# LEDs.net
KiCad netlist of a schematic drawn in Altium Designer
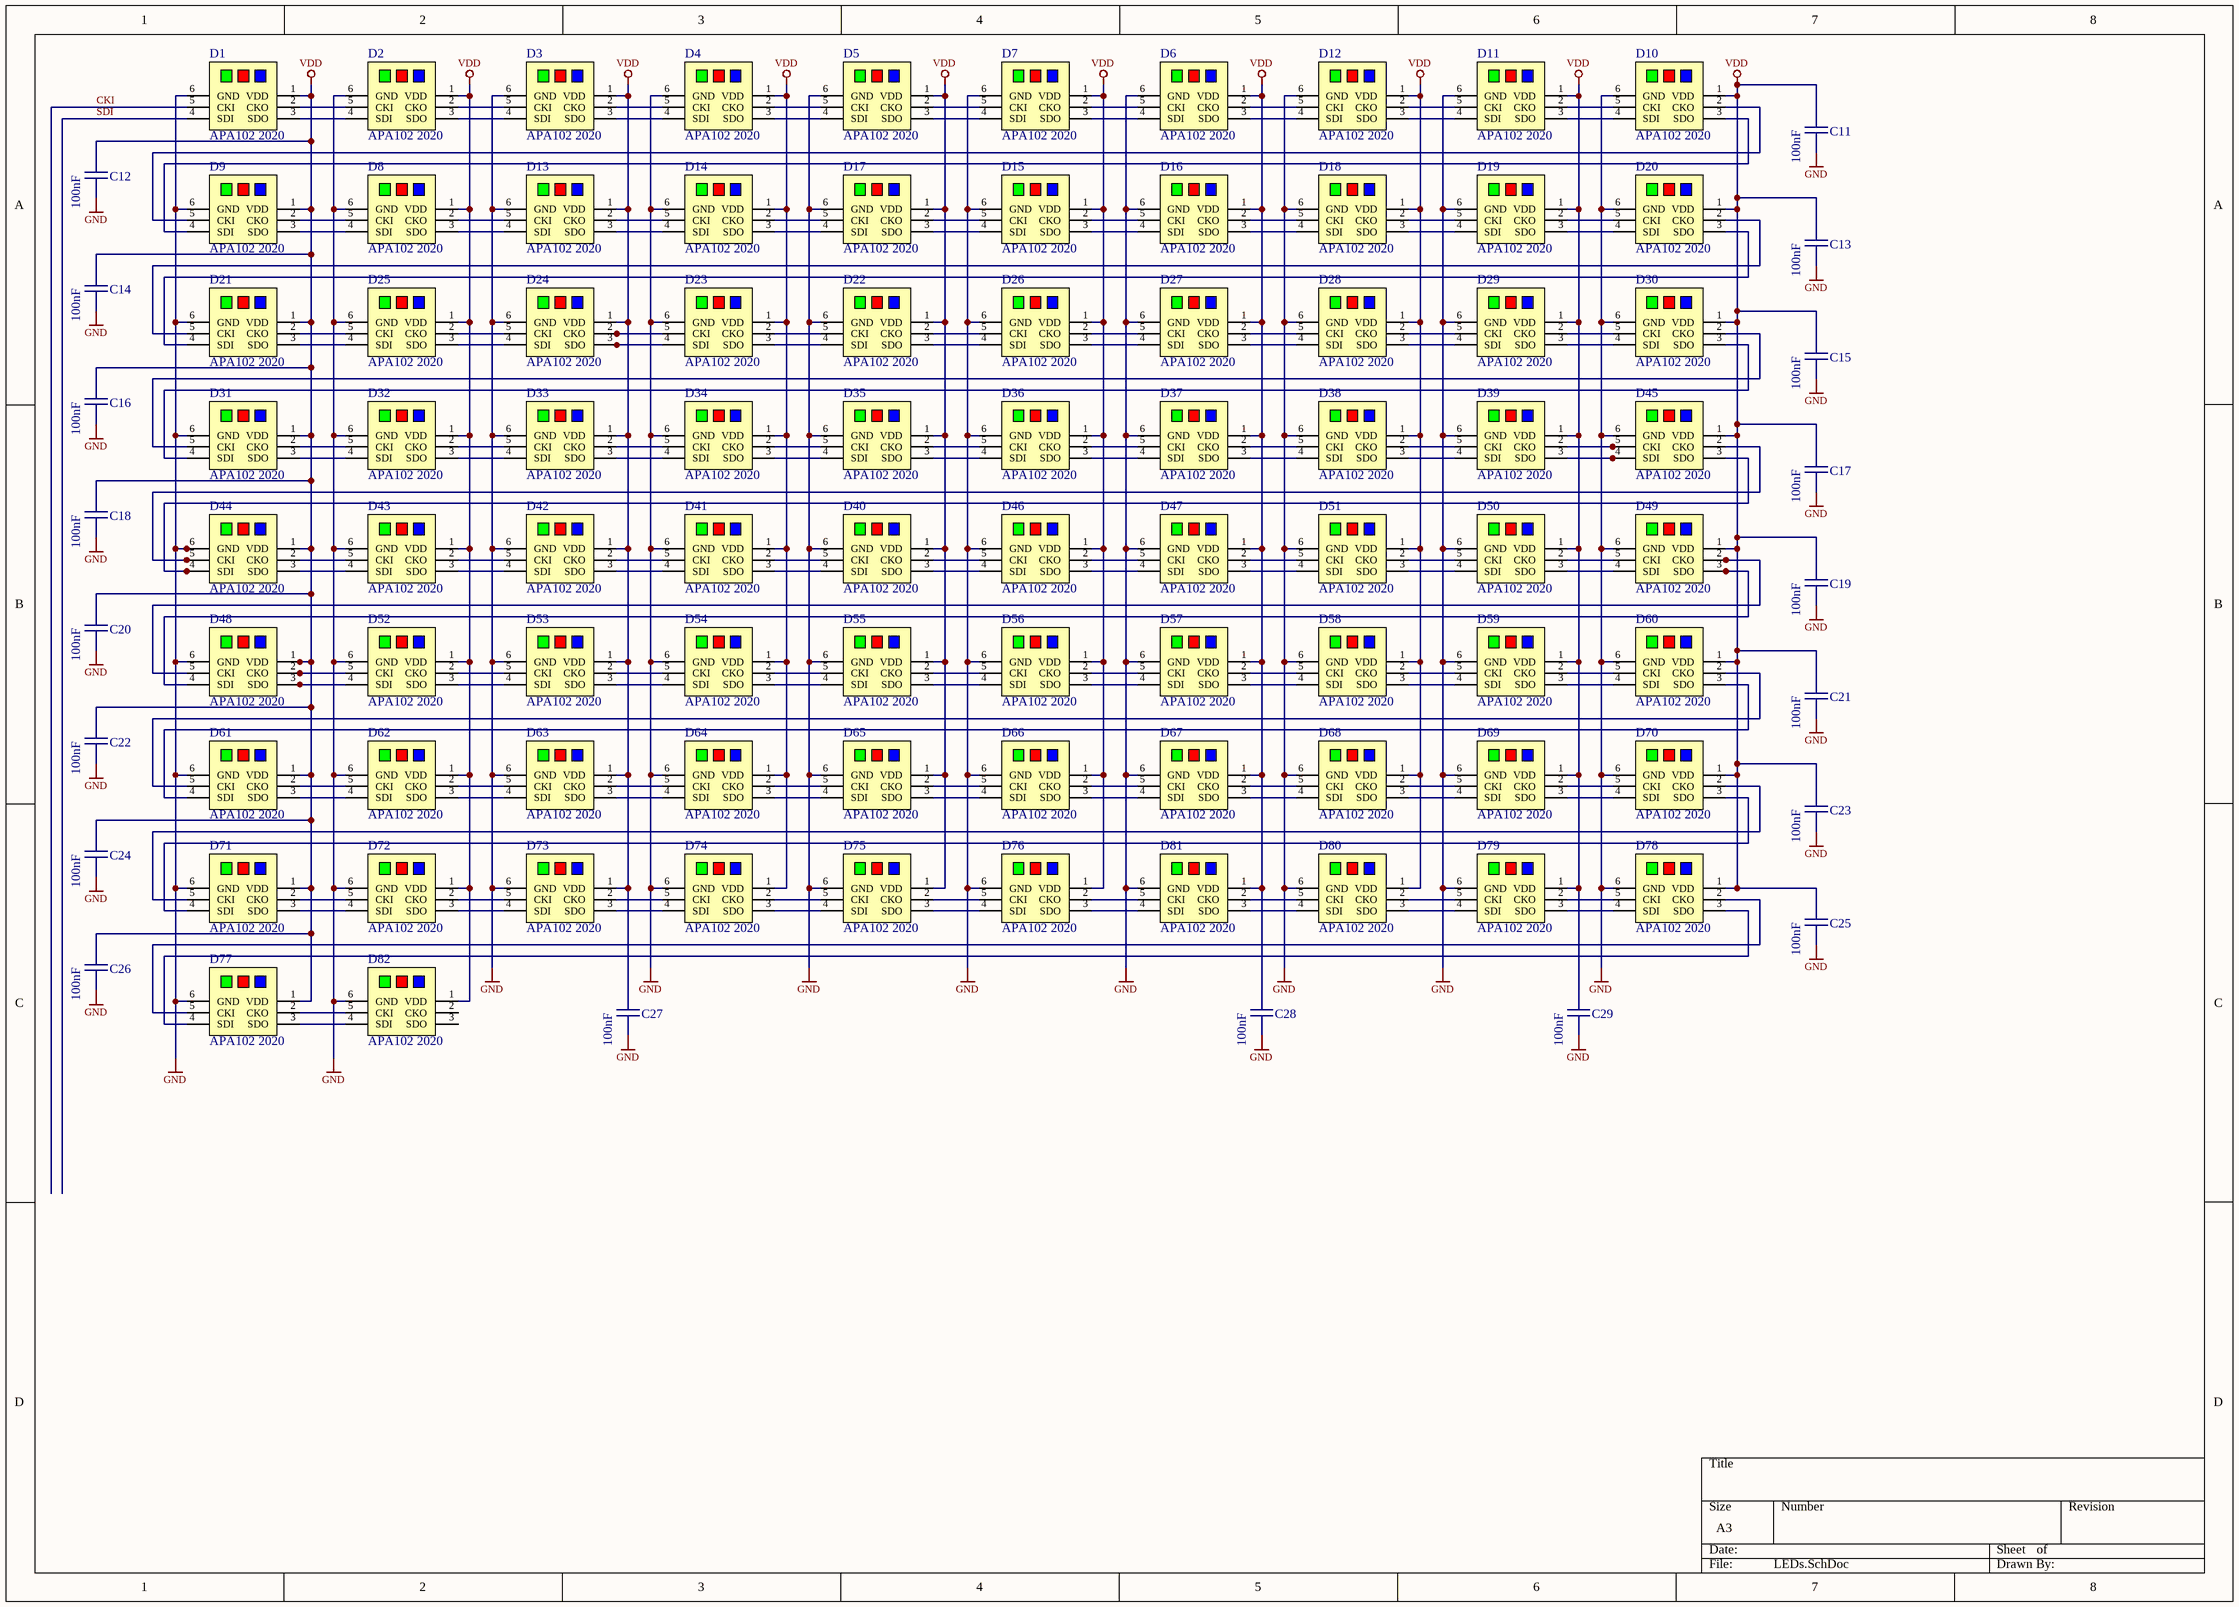
[diagram p0: LEDs.SchDoc]

(export (version "E")
  (design (tool "Eeschema 10.0.6"))
  (components
    (comp (ref "C11")
      (value "100nF")
      (footprint "CAPC0603(1608)55_N")
      (libsource (lib "OVLib_64") (part "CAP"))
    )
    (comp (ref "C12")
      (value "100nF")
      (footprint "CAPC0603(1608)55_N")
      (libsource (lib "OVLib_64") (part "CAP"))
    )
    (comp (ref "C13")
      (value "100nF")
      (footprint "CAPC0603(1608)55_N")
      (libsource (lib "OVLib_64") (part "CAP"))
    )
    (comp (ref "C14")
      (value "100nF")
      (footprint "CAPC0603(1608)55_N")
      (libsource (lib "OVLib_64") (part "CAP"))
    )
    (comp (ref "C15")
      (value "100nF")
      (footprint "CAPC0603(1608)55_N")
      (libsource (lib "OVLib_64") (part "CAP"))
    )
    (comp (ref "C16")
      (value "100nF")
      (footprint "CAPC0603(1608)55_N")
      (libsource (lib "OVLib_64") (part "CAP"))
    )
    (comp (ref "C17")
      (value "100nF")
      (footprint "CAPC0603(1608)55_N")
      (libsource (lib "OVLib_64") (part "CAP"))
    )
    (comp (ref "C18")
      (value "100nF")
      (footprint "CAPC0603(1608)55_N")
      (libsource (lib "OVLib_64") (part "CAP"))
    )
    (comp (ref "C19")
      (value "100nF")
      (footprint "CAPC0603(1608)55_N")
      (libsource (lib "OVLib_64") (part "CAP"))
    )
    (comp (ref "C20")
      (value "100nF")
      (footprint "CAPC0603(1608)55_N")
      (libsource (lib "OVLib_64") (part "CAP"))
    )
    (comp (ref "C21")
      (value "100nF")
      (footprint "CAPC0603(1608)55_N")
      (libsource (lib "OVLib_64") (part "CAP"))
    )
    (comp (ref "C22")
      (value "100nF")
      (footprint "CAPC0603(1608)55_N")
      (libsource (lib "OVLib_64") (part "CAP"))
    )
    (comp (ref "C23")
      (value "100nF")
      (footprint "CAPC0603(1608)55_N")
      (libsource (lib "OVLib_64") (part "CAP"))
    )
    (comp (ref "C24")
      (value "100nF")
      (footprint "CAPC0603(1608)55_N")
      (libsource (lib "OVLib_64") (part "CAP"))
    )
    (comp (ref "C25")
      (value "100nF")
      (footprint "CAPC0603(1608)55_N")
      (libsource (lib "OVLib_64") (part "CAP"))
    )
    (comp (ref "C26")
      (value "100nF")
      (footprint "CAPC0603(1608)55_N")
      (libsource (lib "OVLib_64") (part "CAP"))
    )
    (comp (ref "C27")
      (value "100nF")
      (footprint "CAPC0603(1608)55_N")
      (libsource (lib "OVLib_64") (part "CAP"))
    )
    (comp (ref "C28")
      (value "100nF")
      (footprint "CAPC0603(1608)55_N")
      (libsource (lib "OVLib_64") (part "CAP"))
    )
    (comp (ref "C29")
      (value "100nF")
      (footprint "CAPC0603(1608)55_N")
      (libsource (lib "OVLib_64") (part "CAP"))
    )
    (comp (ref "D1")
      (value "APA102 2020")
      (footprint "APA_RGB_LED_2020")
      (libsource (lib "OVLib_64") (part "LED_RGB_APA102"))
    )
    (comp (ref "D2")
      (value "APA102 2020")
      (footprint "APA_RGB_LED_2020")
      (libsource (lib "OVLib_64") (part "LED_RGB_APA102"))
    )
    (comp (ref "D3")
      (value "APA102 2020")
      (footprint "APA_RGB_LED_2020")
      (libsource (lib "OVLib_64") (part "LED_RGB_APA102"))
    )
    (comp (ref "D4")
      (value "APA102 2020")
      (footprint "APA_RGB_LED_2020")
      (libsource (lib "OVLib_64") (part "LED_RGB_APA102"))
    )
    (comp (ref "D5")
      (value "APA102 2020")
      (footprint "APA_RGB_LED_2020")
      (libsource (lib "OVLib_64") (part "LED_RGB_APA102"))
    )
    (comp (ref "D6")
      (value "APA102 2020")
      (footprint "APA_RGB_LED_2020")
      (libsource (lib "OVLib_64") (part "LED_RGB_APA102"))
    )
    (comp (ref "D7")
      (value "APA102 2020")
      (footprint "APA_RGB_LED_2020")
      (libsource (lib "OVLib_64") (part "LED_RGB_APA102"))
    )
    (comp (ref "D8")
      (value "APA102 2020")
      (footprint "APA_RGB_LED_2020")
      (libsource (lib "OVLib_64") (part "LED_RGB_APA102"))
    )
    (comp (ref "D9")
      (value "APA102 2020")
      (footprint "APA_RGB_LED_2020")
      (libsource (lib "OVLib_64") (part "LED_RGB_APA102"))
    )
    (comp (ref "D10")
      (value "APA102 2020")
      (footprint "APA_RGB_LED_2020")
      (libsource (lib "OVLib_64") (part "LED_RGB_APA102"))
    )
    (comp (ref "D11")
      (value "APA102 2020")
      (footprint "APA_RGB_LED_2020")
      (libsource (lib "OVLib_64") (part "LED_RGB_APA102"))
    )
    (comp (ref "D12")
      (value "APA102 2020")
      (footprint "APA_RGB_LED_2020")
      (libsource (lib "OVLib_64") (part "LED_RGB_APA102"))
    )
    (comp (ref "D13")
      (value "APA102 2020")
      (footprint "APA_RGB_LED_2020")
      (libsource (lib "OVLib_64") (part "LED_RGB_APA102"))
    )
    (comp (ref "D14")
      (value "APA102 2020")
      (footprint "APA_RGB_LED_2020")
      (libsource (lib "OVLib_64") (part "LED_RGB_APA102"))
    )
    (comp (ref "D15")
      (value "APA102 2020")
      (footprint "APA_RGB_LED_2020")
      (libsource (lib "OVLib_64") (part "LED_RGB_APA102"))
    )
    (comp (ref "D16")
      (value "APA102 2020")
      (footprint "APA_RGB_LED_2020")
      (libsource (lib "OVLib_64") (part "LED_RGB_APA102"))
    )
    (comp (ref "D17")
      (value "APA102 2020")
      (footprint "APA_RGB_LED_2020")
      (libsource (lib "OVLib_64") (part "LED_RGB_APA102"))
    )
    (comp (ref "D18")
      (value "APA102 2020")
      (footprint "APA_RGB_LED_2020")
      (libsource (lib "OVLib_64") (part "LED_RGB_APA102"))
    )
    (comp (ref "D19")
      (value "APA102 2020")
      (footprint "APA_RGB_LED_2020")
      (libsource (lib "OVLib_64") (part "LED_RGB_APA102"))
    )
    (comp (ref "D20")
      (value "APA102 2020")
      (footprint "APA_RGB_LED_2020")
      (libsource (lib "OVLib_64") (part "LED_RGB_APA102"))
    )
    (comp (ref "D21")
      (value "APA102 2020")
      (footprint "APA_RGB_LED_2020")
      (libsource (lib "OVLib_64") (part "LED_RGB_APA102"))
    )
    (comp (ref "D22")
      (value "APA102 2020")
      (footprint "APA_RGB_LED_2020")
      (libsource (lib "OVLib_64") (part "LED_RGB_APA102"))
    )
    (comp (ref "D23")
      (value "APA102 2020")
      (footprint "APA_RGB_LED_2020")
      (libsource (lib "OVLib_64") (part "LED_RGB_APA102"))
    )
    (comp (ref "D24")
      (value "APA102 2020")
      (footprint "APA_RGB_LED_2020")
      (libsource (lib "OVLib_64") (part "LED_RGB_APA102"))
    )
    (comp (ref "D25")
      (value "APA102 2020")
      (footprint "APA_RGB_LED_2020")
      (libsource (lib "OVLib_64") (part "LED_RGB_APA102"))
    )
    (comp (ref "D26")
      (value "APA102 2020")
      (footprint "APA_RGB_LED_2020")
      (libsource (lib "OVLib_64") (part "LED_RGB_APA102"))
    )
    (comp (ref "D27")
      (value "APA102 2020")
      (footprint "APA_RGB_LED_2020")
      (libsource (lib "OVLib_64") (part "LED_RGB_APA102"))
    )
    (comp (ref "D28")
      (value "APA102 2020")
      (footprint "APA_RGB_LED_2020")
      (libsource (lib "OVLib_64") (part "LED_RGB_APA102"))
    )
    (comp (ref "D29")
      (value "APA102 2020")
      (footprint "APA_RGB_LED_2020")
      (libsource (lib "OVLib_64") (part "LED_RGB_APA102"))
    )
    (comp (ref "D30")
      (value "APA102 2020")
      (footprint "APA_RGB_LED_2020")
      (libsource (lib "OVLib_64") (part "LED_RGB_APA102"))
    )
    (comp (ref "D31")
      (value "APA102 2020")
      (footprint "APA_RGB_LED_2020")
      (libsource (lib "OVLib_64") (part "LED_RGB_APA102"))
    )
    (comp (ref "D32")
      (value "APA102 2020")
      (footprint "APA_RGB_LED_2020")
      (libsource (lib "OVLib_64") (part "LED_RGB_APA102"))
    )
    (comp (ref "D33")
      (value "APA102 2020")
      (footprint "APA_RGB_LED_2020")
      (libsource (lib "OVLib_64") (part "LED_RGB_APA102"))
    )
    (comp (ref "D34")
      (value "APA102 2020")
      (footprint "APA_RGB_LED_2020")
      (libsource (lib "OVLib_64") (part "LED_RGB_APA102"))
    )
    (comp (ref "D35")
      (value "APA102 2020")
      (footprint "APA_RGB_LED_2020")
      (libsource (lib "OVLib_64") (part "LED_RGB_APA102"))
    )
    (comp (ref "D36")
      (value "APA102 2020")
      (footprint "APA_RGB_LED_2020")
      (libsource (lib "OVLib_64") (part "LED_RGB_APA102"))
    )
    (comp (ref "D37")
      (value "APA102 2020")
      (footprint "APA_RGB_LED_2020")
      (libsource (lib "OVLib_64") (part "LED_RGB_APA102"))
    )
    (comp (ref "D38")
      (value "APA102 2020")
      (footprint "APA_RGB_LED_2020")
      (libsource (lib "OVLib_64") (part "LED_RGB_APA102"))
    )
    (comp (ref "D39")
      (value "APA102 2020")
      (footprint "APA_RGB_LED_2020")
      (libsource (lib "OVLib_64") (part "LED_RGB_APA102"))
    )
    (comp (ref "D40")
      (value "APA102 2020")
      (footprint "APA_RGB_LED_2020")
      (libsource (lib "OVLib_64") (part "LED_RGB_APA102"))
    )
    (comp (ref "D41")
      (value "APA102 2020")
      (footprint "APA_RGB_LED_2020")
      (libsource (lib "OVLib_64") (part "LED_RGB_APA102"))
    )
    (comp (ref "D42")
      (value "APA102 2020")
      (footprint "APA_RGB_LED_2020")
      (libsource (lib "OVLib_64") (part "LED_RGB_APA102"))
    )
    (comp (ref "D43")
      (value "APA102 2020")
      (footprint "APA_RGB_LED_2020")
      (libsource (lib "OVLib_64") (part "LED_RGB_APA102"))
    )
    (comp (ref "D44")
      (value "APA102 2020")
      (footprint "APA_RGB_LED_2020")
      (libsource (lib "OVLib_64") (part "LED_RGB_APA102"))
    )
    (comp (ref "D45")
      (value "APA102 2020")
      (footprint "APA_RGB_LED_2020")
      (libsource (lib "OVLib_64") (part "LED_RGB_APA102"))
    )
    (comp (ref "D46")
      (value "APA102 2020")
      (footprint "APA_RGB_LED_2020")
      (libsource (lib "OVLib_64") (part "LED_RGB_APA102"))
    )
    (comp (ref "D47")
      (value "APA102 2020")
      (footprint "APA_RGB_LED_2020")
      (libsource (lib "OVLib_64") (part "LED_RGB_APA102"))
    )
    (comp (ref "D48")
      (value "APA102 2020")
      (footprint "APA_RGB_LED_2020")
      (libsource (lib "OVLib_64") (part "LED_RGB_APA102"))
    )
    (comp (ref "D49")
      (value "APA102 2020")
      (footprint "APA_RGB_LED_2020")
      (libsource (lib "OVLib_64") (part "LED_RGB_APA102"))
    )
    (comp (ref "D50")
      (value "APA102 2020")
      (footprint "APA_RGB_LED_2020")
      (libsource (lib "OVLib_64") (part "LED_RGB_APA102"))
    )
    (comp (ref "D51")
      (value "APA102 2020")
      (footprint "APA_RGB_LED_2020")
      (libsource (lib "OVLib_64") (part "LED_RGB_APA102"))
    )
    (comp (ref "D52")
      (value "APA102 2020")
      (footprint "APA_RGB_LED_2020")
      (libsource (lib "OVLib_64") (part "LED_RGB_APA102"))
    )
    (comp (ref "D53")
      (value "APA102 2020")
      (footprint "APA_RGB_LED_2020")
      (libsource (lib "OVLib_64") (part "LED_RGB_APA102"))
    )
    (comp (ref "D54")
      (value "APA102 2020")
      (footprint "APA_RGB_LED_2020")
      (libsource (lib "OVLib_64") (part "LED_RGB_APA102"))
    )
    (comp (ref "D55")
      (value "APA102 2020")
      (footprint "APA_RGB_LED_2020")
      (libsource (lib "OVLib_64") (part "LED_RGB_APA102"))
    )
    (comp (ref "D56")
      (value "APA102 2020")
      (footprint "APA_RGB_LED_2020")
      (libsource (lib "OVLib_64") (part "LED_RGB_APA102"))
    )
    (comp (ref "D57")
      (value "APA102 2020")
      (footprint "APA_RGB_LED_2020")
      (libsource (lib "OVLib_64") (part "LED_RGB_APA102"))
    )
    (comp (ref "D58")
      (value "APA102 2020")
      (footprint "APA_RGB_LED_2020")
      (libsource (lib "OVLib_64") (part "LED_RGB_APA102"))
    )
    (comp (ref "D59")
      (value "APA102 2020")
      (footprint "APA_RGB_LED_2020")
      (libsource (lib "OVLib_64") (part "LED_RGB_APA102"))
    )
    (comp (ref "D60")
      (value "APA102 2020")
      (footprint "APA_RGB_LED_2020")
      (libsource (lib "OVLib_64") (part "LED_RGB_APA102"))
    )
    (comp (ref "D61")
      (value "APA102 2020")
      (footprint "APA_RGB_LED_2020")
      (libsource (lib "OVLib_64") (part "LED_RGB_APA102"))
    )
    (comp (ref "D62")
      (value "APA102 2020")
      (footprint "APA_RGB_LED_2020")
      (libsource (lib "OVLib_64") (part "LED_RGB_APA102"))
    )
    (comp (ref "D63")
      (value "APA102 2020")
      (footprint "APA_RGB_LED_2020")
      (libsource (lib "OVLib_64") (part "LED_RGB_APA102"))
    )
    (comp (ref "D64")
      (value "APA102 2020")
      (footprint "APA_RGB_LED_2020")
      (libsource (lib "OVLib_64") (part "LED_RGB_APA102"))
    )
    (comp (ref "D65")
      (value "APA102 2020")
      (footprint "APA_RGB_LED_2020")
      (libsource (lib "OVLib_64") (part "LED_RGB_APA102"))
    )
    (comp (ref "D66")
      (value "APA102 2020")
      (footprint "APA_RGB_LED_2020")
      (libsource (lib "OVLib_64") (part "LED_RGB_APA102"))
    )
    (comp (ref "D67")
      (value "APA102 2020")
      (footprint "APA_RGB_LED_2020")
      (libsource (lib "OVLib_64") (part "LED_RGB_APA102"))
    )
    (comp (ref "D68")
      (value "APA102 2020")
      (footprint "APA_RGB_LED_2020")
      (libsource (lib "OVLib_64") (part "LED_RGB_APA102"))
    )
    (comp (ref "D69")
      (value "APA102 2020")
      (footprint "APA_RGB_LED_2020")
      (libsource (lib "OVLib_64") (part "LED_RGB_APA102"))
    )
    (comp (ref "D70")
      (value "APA102 2020")
      (footprint "APA_RGB_LED_2020")
      (libsource (lib "OVLib_64") (part "LED_RGB_APA102"))
    )
    (comp (ref "D71")
      (value "APA102 2020")
      (footprint "APA_RGB_LED_2020")
      (libsource (lib "OVLib_64") (part "LED_RGB_APA102"))
    )
    (comp (ref "D72")
      (value "APA102 2020")
      (footprint "APA_RGB_LED_2020")
      (libsource (lib "OVLib_64") (part "LED_RGB_APA102"))
    )
    (comp (ref "D73")
      (value "APA102 2020")
      (footprint "APA_RGB_LED_2020")
      (libsource (lib "OVLib_64") (part "LED_RGB_APA102"))
    )
    (comp (ref "D74")
      (value "APA102 2020")
      (footprint "APA_RGB_LED_2020")
      (libsource (lib "OVLib_64") (part "LED_RGB_APA102"))
    )
    (comp (ref "D75")
      (value "APA102 2020")
      (footprint "APA_RGB_LED_2020")
      (libsource (lib "OVLib_64") (part "LED_RGB_APA102"))
    )
    (comp (ref "D76")
      (value "APA102 2020")
      (footprint "APA_RGB_LED_2020")
      (libsource (lib "OVLib_64") (part "LED_RGB_APA102"))
    )
    (comp (ref "D77")
      (value "APA102 2020")
      (footprint "APA_RGB_LED_2020")
      (libsource (lib "OVLib_64") (part "LED_RGB_APA102"))
    )
    (comp (ref "D78")
      (value "APA102 2020")
      (footprint "APA_RGB_LED_2020")
      (libsource (lib "OVLib_64") (part "LED_RGB_APA102"))
    )
    (comp (ref "D79")
      (value "APA102 2020")
      (footprint "APA_RGB_LED_2020")
      (libsource (lib "OVLib_64") (part "LED_RGB_APA102"))
    )
    (comp (ref "D80")
      (value "APA102 2020")
      (footprint "APA_RGB_LED_2020")
      (libsource (lib "OVLib_64") (part "LED_RGB_APA102"))
    )
    (comp (ref "D81")
      (value "APA102 2020")
      (footprint "APA_RGB_LED_2020")
      (libsource (lib "OVLib_64") (part "LED_RGB_APA102"))
    )
    (comp (ref "D82")
      (value "APA102 2020")
      (footprint "APA_RGB_LED_2020")
      (libsource (lib "OVLib_64") (part "LED_RGB_APA102"))
    )
  )
  (nets
    (net (code "1") (name "/CKI") (class "Default")
      (node (ref "D1") (pin "5") (pinfunction "CKI_5") (pintype "passive"))
    )
    (net (code "2") (name "/SDI") (class "Default")
      (node (ref "D1") (pin "4") (pinfunction "SDI_4") (pintype "passive"))
    )
    (net (code "3") (name "GND") (class "Default")
      (node (ref "C11") (pin "1") (pinfunction "1_1") (pintype "passive"))
      (node (ref "C12") (pin "1") (pinfunction "1_1") (pintype "passive"))
      (node (ref "C13") (pin "1") (pinfunction "1_1") (pintype "passive"))
      (node (ref "C14") (pin "1") (pinfunction "1_1") (pintype "passive"))
      (node (ref "C15") (pin "1") (pinfunction "1_1") (pintype "passive"))
      (node (ref "C16") (pin "1") (pinfunction "1_1") (pintype "passive"))
      (node (ref "C17") (pin "1") (pinfunction "1_1") (pintype "passive"))
      (node (ref "C18") (pin "1") (pinfunction "1_1") (pintype "passive"))
      (node (ref "C19") (pin "1") (pinfunction "1_1") (pintype "passive"))
      (node (ref "C20") (pin "1") (pinfunction "1_1") (pintype "passive"))
      (node (ref "C21") (pin "1") (pinfunction "1_1") (pintype "passive"))
      (node (ref "C22") (pin "1") (pinfunction "1_1") (pintype "passive"))
      (node (ref "C23") (pin "1") (pinfunction "1_1") (pintype "passive"))
      (node (ref "C24") (pin "1") (pinfunction "1_1") (pintype "passive"))
      (node (ref "C25") (pin "1") (pinfunction "1_1") (pintype "passive"))
      (node (ref "C26") (pin "1") (pinfunction "1_1") (pintype "passive"))
      (node (ref "C27") (pin "1") (pinfunction "1_1") (pintype "passive"))
      (node (ref "C28") (pin "1") (pinfunction "1_1") (pintype "passive"))
      (node (ref "C29") (pin "1") (pinfunction "1_1") (pintype "passive"))
      (node (ref "D1") (pin "6") (pinfunction "GND_6") (pintype "passive"))
      (node (ref "D10") (pin "6") (pinfunction "GND_6") (pintype "passive"))
      (node (ref "D11") (pin "6") (pinfunction "GND_6") (pintype "passive"))
      (node (ref "D12") (pin "6") (pinfunction "GND_6") (pintype "passive"))
      (node (ref "D13") (pin "6") (pinfunction "GND_6") (pintype "passive"))
      (node (ref "D14") (pin "6") (pinfunction "GND_6") (pintype "passive"))
      (node (ref "D15") (pin "6") (pinfunction "GND_6") (pintype "passive"))
      (node (ref "D16") (pin "6") (pinfunction "GND_6") (pintype "passive"))
      (node (ref "D17") (pin "6") (pinfunction "GND_6") (pintype "passive"))
      (node (ref "D18") (pin "6") (pinfunction "GND_6") (pintype "passive"))
      (node (ref "D19") (pin "6") (pinfunction "GND_6") (pintype "passive"))
      (node (ref "D2") (pin "6") (pinfunction "GND_6") (pintype "passive"))
      (node (ref "D20") (pin "6") (pinfunction "GND_6") (pintype "passive"))
      (node (ref "D21") (pin "6") (pinfunction "GND_6") (pintype "passive"))
      (node (ref "D22") (pin "6") (pinfunction "GND_6") (pintype "passive"))
      (node (ref "D23") (pin "6") (pinfunction "GND_6") (pintype "passive"))
      (node (ref "D24") (pin "6") (pinfunction "GND_6") (pintype "passive"))
      (node (ref "D25") (pin "6") (pinfunction "GND_6") (pintype "passive"))
      (node (ref "D26") (pin "6") (pinfunction "GND_6") (pintype "passive"))
      (node (ref "D27") (pin "6") (pinfunction "GND_6") (pintype "passive"))
      (node (ref "D28") (pin "6") (pinfunction "GND_6") (pintype "passive"))
      (node (ref "D29") (pin "6") (pinfunction "GND_6") (pintype "passive"))
      (node (ref "D3") (pin "6") (pinfunction "GND_6") (pintype "passive"))
      (node (ref "D30") (pin "6") (pinfunction "GND_6") (pintype "passive"))
      (node (ref "D31") (pin "6") (pinfunction "GND_6") (pintype "passive"))
      (node (ref "D32") (pin "6") (pinfunction "GND_6") (pintype "passive"))
      (node (ref "D33") (pin "6") (pinfunction "GND_6") (pintype "passive"))
      (node (ref "D34") (pin "6") (pinfunction "GND_6") (pintype "passive"))
      (node (ref "D35") (pin "6") (pinfunction "GND_6") (pintype "passive"))
      (node (ref "D36") (pin "6") (pinfunction "GND_6") (pintype "passive"))
      (node (ref "D37") (pin "6") (pinfunction "GND_6") (pintype "passive"))
      (node (ref "D38") (pin "6") (pinfunction "GND_6") (pintype "passive"))
      (node (ref "D39") (pin "6") (pinfunction "GND_6") (pintype "passive"))
      (node (ref "D4") (pin "6") (pinfunction "GND_6") (pintype "passive"))
      (node (ref "D40") (pin "6") (pinfunction "GND_6") (pintype "passive"))
      (node (ref "D41") (pin "6") (pinfunction "GND_6") (pintype "passive"))
      (node (ref "D42") (pin "6") (pinfunction "GND_6") (pintype "passive"))
      (node (ref "D43") (pin "6") (pinfunction "GND_6") (pintype "passive"))
      (node (ref "D44") (pin "6") (pinfunction "GND_6") (pintype "passive"))
      (node (ref "D45") (pin "6") (pinfunction "GND_6") (pintype "passive"))
      (node (ref "D46") (pin "6") (pinfunction "GND_6") (pintype "passive"))
      (node (ref "D47") (pin "6") (pinfunction "GND_6") (pintype "passive"))
      (node (ref "D48") (pin "6") (pinfunction "GND_6") (pintype "passive"))
      (node (ref "D49") (pin "6") (pinfunction "GND_6") (pintype "passive"))
      (node (ref "D5") (pin "6") (pinfunction "GND_6") (pintype "passive"))
      (node (ref "D50") (pin "6") (pinfunction "GND_6") (pintype "passive"))
      (node (ref "D51") (pin "6") (pinfunction "GND_6") (pintype "passive"))
      (node (ref "D52") (pin "6") (pinfunction "GND_6") (pintype "passive"))
      (node (ref "D53") (pin "6") (pinfunction "GND_6") (pintype "passive"))
      (node (ref "D54") (pin "6") (pinfunction "GND_6") (pintype "passive"))
      (node (ref "D55") (pin "6") (pinfunction "GND_6") (pintype "passive"))
      (node (ref "D56") (pin "6") (pinfunction "GND_6") (pintype "passive"))
      (node (ref "D57") (pin "6") (pinfunction "GND_6") (pintype "passive"))
      (node (ref "D58") (pin "6") (pinfunction "GND_6") (pintype "passive"))
      (node (ref "D59") (pin "6") (pinfunction "GND_6") (pintype "passive"))
      (node (ref "D6") (pin "6") (pinfunction "GND_6") (pintype "passive"))
      (node (ref "D60") (pin "6") (pinfunction "GND_6") (pintype "passive"))
      (node (ref "D61") (pin "6") (pinfunction "GND_6") (pintype "passive"))
      (node (ref "D62") (pin "6") (pinfunction "GND_6") (pintype "passive"))
      (node (ref "D63") (pin "6") (pinfunction "GND_6") (pintype "passive"))
      (node (ref "D64") (pin "6") (pinfunction "GND_6") (pintype "passive"))
      (node (ref "D65") (pin "6") (pinfunction "GND_6") (pintype "passive"))
      (node (ref "D66") (pin "6") (pinfunction "GND_6") (pintype "passive"))
      (node (ref "D67") (pin "6") (pinfunction "GND_6") (pintype "passive"))
      (node (ref "D68") (pin "6") (pinfunction "GND_6") (pintype "passive"))
      (node (ref "D69") (pin "6") (pinfunction "GND_6") (pintype "passive"))
      (node (ref "D7") (pin "6") (pinfunction "GND_6") (pintype "passive"))
      (node (ref "D70") (pin "6") (pinfunction "GND_6") (pintype "passive"))
      (node (ref "D71") (pin "6") (pinfunction "GND_6") (pintype "passive"))
      (node (ref "D72") (pin "6") (pinfunction "GND_6") (pintype "passive"))
      (node (ref "D73") (pin "6") (pinfunction "GND_6") (pintype "passive"))
      (node (ref "D74") (pin "6") (pinfunction "GND_6") (pintype "passive"))
      (node (ref "D75") (pin "6") (pinfunction "GND_6") (pintype "passive"))
      (node (ref "D76") (pin "6") (pinfunction "GND_6") (pintype "passive"))
      (node (ref "D77") (pin "6") (pinfunction "GND_6") (pintype "passive"))
      (node (ref "D78") (pin "6") (pinfunction "GND_6") (pintype "passive"))
      (node (ref "D79") (pin "6") (pinfunction "GND_6") (pintype "passive"))
      (node (ref "D8") (pin "6") (pinfunction "GND_6") (pintype "passive"))
      (node (ref "D80") (pin "6") (pinfunction "GND_6") (pintype "passive"))
      (node (ref "D81") (pin "6") (pinfunction "GND_6") (pintype "passive"))
      (node (ref "D82") (pin "6") (pinfunction "GND_6") (pintype "passive"))
      (node (ref "D9") (pin "6") (pinfunction "GND_6") (pintype "passive"))
    )
    (net (code "4") (name "Net-(D1-CKO)") (class "Default")
      (node (ref "D1") (pin "2") (pinfunction "CKO_2") (pintype "passive"))
      (node (ref "D2") (pin "5") (pinfunction "CKI_5") (pintype "passive"))
    )
    (net (code "5") (name "Net-(D1-SDO)") (class "Default")
      (node (ref "D1") (pin "3") (pinfunction "SDO_3") (pintype "passive"))
      (node (ref "D2") (pin "4") (pinfunction "SDI_4") (pintype "passive"))
    )
    (net (code "6") (name "Net-(D2-CKO)") (class "Default")
      (node (ref "D2") (pin "2") (pinfunction "CKO_2") (pintype "passive"))
      (node (ref "D3") (pin "5") (pinfunction "CKI_5") (pintype "passive"))
    )
    (net (code "7") (name "Net-(D2-SDO)") (class "Default")
      (node (ref "D2") (pin "3") (pinfunction "SDO_3") (pintype "passive"))
      (node (ref "D3") (pin "4") (pinfunction "SDI_4") (pintype "passive"))
    )
    (net (code "8") (name "Net-(D3-CKO)") (class "Default")
      (node (ref "D3") (pin "2") (pinfunction "CKO_2") (pintype "passive"))
      (node (ref "D4") (pin "5") (pinfunction "CKI_5") (pintype "passive"))
    )
    (net (code "9") (name "Net-(D3-SDO)") (class "Default")
      (node (ref "D3") (pin "3") (pinfunction "SDO_3") (pintype "passive"))
      (node (ref "D4") (pin "4") (pinfunction "SDI_4") (pintype "passive"))
    )
    (net (code "10") (name "Net-(D4-CKO)") (class "Default")
      (node (ref "D4") (pin "2") (pinfunction "CKO_2") (pintype "passive"))
      (node (ref "D5") (pin "5") (pinfunction "CKI_5") (pintype "passive"))
    )
    (net (code "11") (name "Net-(D4-SDO)") (class "Default")
      (node (ref "D4") (pin "3") (pinfunction "SDO_3") (pintype "passive"))
      (node (ref "D5") (pin "4") (pinfunction "SDI_4") (pintype "passive"))
    )
    (net (code "12") (name "Net-(D5-CKO)") (class "Default")
      (node (ref "D5") (pin "2") (pinfunction "CKO_2") (pintype "passive"))
      (node (ref "D7") (pin "5") (pinfunction "CKI_5") (pintype "passive"))
    )
    (net (code "13") (name "Net-(D5-SDO)") (class "Default")
      (node (ref "D5") (pin "3") (pinfunction "SDO_3") (pintype "passive"))
      (node (ref "D7") (pin "4") (pinfunction "SDI_4") (pintype "passive"))
    )
    (net (code "14") (name "Net-(D6-CKI)") (class "Default")
      (node (ref "D6") (pin "5") (pinfunction "CKI_5") (pintype "passive"))
      (node (ref "D7") (pin "2") (pinfunction "CKO_2") (pintype "passive"))
    )
    (net (code "15") (name "Net-(D6-SDI)") (class "Default")
      (node (ref "D6") (pin "4") (pinfunction "SDI_4") (pintype "passive"))
      (node (ref "D7") (pin "3") (pinfunction "SDO_3") (pintype "passive"))
    )
    (net (code "16") (name "Net-(D8-CKI)") (class "Default")
      (node (ref "D8") (pin "5") (pinfunction "CKI_5") (pintype "passive"))
      (node (ref "D9") (pin "2") (pinfunction "CKO_2") (pintype "passive"))
    )
    (net (code "17") (name "Net-(D8-SDI)") (class "Default")
      (node (ref "D8") (pin "4") (pinfunction "SDI_4") (pintype "passive"))
      (node (ref "D9") (pin "3") (pinfunction "SDO_3") (pintype "passive"))
    )
    (net (code "18") (name "Net-(D10-CKI)") (class "Default")
      (node (ref "D10") (pin "5") (pinfunction "CKI_5") (pintype "passive"))
      (node (ref "D11") (pin "2") (pinfunction "CKO_2") (pintype "passive"))
    )
    (net (code "19") (name "Net-(D10-CKO)") (class "Default")
      (node (ref "D10") (pin "2") (pinfunction "CKO_2") (pintype "passive"))
      (node (ref "D9") (pin "5") (pinfunction "CKI_5") (pintype "passive"))
    )
    (net (code "20") (name "Net-(D10-SDI)") (class "Default")
      (node (ref "D10") (pin "4") (pinfunction "SDI_4") (pintype "passive"))
      (node (ref "D11") (pin "3") (pinfunction "SDO_3") (pintype "passive"))
    )
    (net (code "21") (name "Net-(D10-SDO)") (class "Default")
      (node (ref "D10") (pin "3") (pinfunction "SDO_3") (pintype "passive"))
      (node (ref "D9") (pin "4") (pinfunction "SDI_4") (pintype "passive"))
    )
    (net (code "22") (name "Net-(D11-CKI)") (class "Default")
      (node (ref "D11") (pin "5") (pinfunction "CKI_5") (pintype "passive"))
      (node (ref "D12") (pin "2") (pinfunction "CKO_2") (pintype "passive"))
    )
    (net (code "23") (name "Net-(D11-SDI)") (class "Default")
      (node (ref "D11") (pin "4") (pinfunction "SDI_4") (pintype "passive"))
      (node (ref "D12") (pin "3") (pinfunction "SDO_3") (pintype "passive"))
    )
    (net (code "24") (name "Net-(D12-CKI)") (class "Default")
      (node (ref "D12") (pin "5") (pinfunction "CKI_5") (pintype "passive"))
      (node (ref "D6") (pin "2") (pinfunction "CKO_2") (pintype "passive"))
    )
    (net (code "25") (name "Net-(D12-SDI)") (class "Default")
      (node (ref "D12") (pin "4") (pinfunction "SDI_4") (pintype "passive"))
      (node (ref "D6") (pin "3") (pinfunction "SDO_3") (pintype "passive"))
    )
    (net (code "26") (name "Net-(D13-CKI)") (class "Default")
      (node (ref "D13") (pin "5") (pinfunction "CKI_5") (pintype "passive"))
      (node (ref "D8") (pin "2") (pinfunction "CKO_2") (pintype "passive"))
    )
    (net (code "27") (name "Net-(D13-CKO)") (class "Default")
      (node (ref "D13") (pin "2") (pinfunction "CKO_2") (pintype "passive"))
      (node (ref "D14") (pin "5") (pinfunction "CKI_5") (pintype "passive"))
    )
    (net (code "28") (name "Net-(D13-SDI)") (class "Default")
      (node (ref "D13") (pin "4") (pinfunction "SDI_4") (pintype "passive"))
      (node (ref "D8") (pin "3") (pinfunction "SDO_3") (pintype "passive"))
    )
    (net (code "29") (name "Net-(D13-SDO)") (class "Default")
      (node (ref "D13") (pin "3") (pinfunction "SDO_3") (pintype "passive"))
      (node (ref "D14") (pin "4") (pinfunction "SDI_4") (pintype "passive"))
    )
    (net (code "30") (name "Net-(D14-CKO)") (class "Default")
      (node (ref "D14") (pin "2") (pinfunction "CKO_2") (pintype "passive"))
      (node (ref "D17") (pin "5") (pinfunction "CKI_5") (pintype "passive"))
    )
    (net (code "31") (name "Net-(D14-SDO)") (class "Default")
      (node (ref "D14") (pin "3") (pinfunction "SDO_3") (pintype "passive"))
      (node (ref "D17") (pin "4") (pinfunction "SDI_4") (pintype "passive"))
    )
    (net (code "32") (name "Net-(D15-CKI)") (class "Default")
      (node (ref "D15") (pin "5") (pinfunction "CKI_5") (pintype "passive"))
      (node (ref "D17") (pin "2") (pinfunction "CKO_2") (pintype "passive"))
    )
    (net (code "33") (name "Net-(D15-CKO)") (class "Default")
      (node (ref "D15") (pin "2") (pinfunction "CKO_2") (pintype "passive"))
      (node (ref "D16") (pin "5") (pinfunction "CKI_5") (pintype "passive"))
    )
    (net (code "34") (name "Net-(D15-SDI)") (class "Default")
      (node (ref "D15") (pin "4") (pinfunction "SDI_4") (pintype "passive"))
      (node (ref "D17") (pin "3") (pinfunction "SDO_3") (pintype "passive"))
    )
    (net (code "35") (name "Net-(D15-SDO)") (class "Default")
      (node (ref "D15") (pin "3") (pinfunction "SDO_3") (pintype "passive"))
      (node (ref "D16") (pin "4") (pinfunction "SDI_4") (pintype "passive"))
    )
    (net (code "36") (name "Net-(D16-CKO)") (class "Default")
      (node (ref "D16") (pin "2") (pinfunction "CKO_2") (pintype "passive"))
      (node (ref "D18") (pin "5") (pinfunction "CKI_5") (pintype "passive"))
    )
    (net (code "37") (name "Net-(D16-SDO)") (class "Default")
      (node (ref "D16") (pin "3") (pinfunction "SDO_3") (pintype "passive"))
      (node (ref "D18") (pin "4") (pinfunction "SDI_4") (pintype "passive"))
    )
    (net (code "38") (name "Net-(D18-CKO)") (class "Default")
      (node (ref "D18") (pin "2") (pinfunction "CKO_2") (pintype "passive"))
      (node (ref "D19") (pin "5") (pinfunction "CKI_5") (pintype "passive"))
    )
    (net (code "39") (name "Net-(D18-SDO)") (class "Default")
      (node (ref "D18") (pin "3") (pinfunction "SDO_3") (pintype "passive"))
      (node (ref "D19") (pin "4") (pinfunction "SDI_4") (pintype "passive"))
    )
    (net (code "40") (name "Net-(D19-CKO)") (class "Default")
      (node (ref "D19") (pin "2") (pinfunction "CKO_2") (pintype "passive"))
      (node (ref "D20") (pin "5") (pinfunction "CKI_5") (pintype "passive"))
    )
    (net (code "41") (name "Net-(D19-SDO)") (class "Default")
      (node (ref "D19") (pin "3") (pinfunction "SDO_3") (pintype "passive"))
      (node (ref "D20") (pin "4") (pinfunction "SDI_4") (pintype "passive"))
    )
    (net (code "42") (name "Net-(D20-CKO)") (class "Default")
      (node (ref "D20") (pin "2") (pinfunction "CKO_2") (pintype "passive"))
      (node (ref "D21") (pin "5") (pinfunction "CKI_5") (pintype "passive"))
    )
    (net (code "43") (name "Net-(D20-SDO)") (class "Default")
      (node (ref "D20") (pin "3") (pinfunction "SDO_3") (pintype "passive"))
      (node (ref "D21") (pin "4") (pinfunction "SDI_4") (pintype "passive"))
    )
    (net (code "44") (name "Net-(D21-CKO)") (class "Default")
      (node (ref "D21") (pin "2") (pinfunction "CKO_2") (pintype "passive"))
      (node (ref "D25") (pin "5") (pinfunction "CKI_5") (pintype "passive"))
    )
    (net (code "45") (name "Net-(D21-SDO)") (class "Default")
      (node (ref "D21") (pin "3") (pinfunction "SDO_3") (pintype "passive"))
      (node (ref "D25") (pin "4") (pinfunction "SDI_4") (pintype "passive"))
    )
    (net (code "46") (name "Net-(D22-CKI)") (class "Default")
      (node (ref "D22") (pin "5") (pinfunction "CKI_5") (pintype "passive"))
      (node (ref "D23") (pin "2") (pinfunction "CKO_2") (pintype "passive"))
    )
    (net (code "47") (name "Net-(D22-CKO)") (class "Default")
      (node (ref "D22") (pin "2") (pinfunction "CKO_2") (pintype "passive"))
      (node (ref "D26") (pin "5") (pinfunction "CKI_5") (pintype "passive"))
    )
    (net (code "48") (name "Net-(D22-SDI)") (class "Default")
      (node (ref "D22") (pin "4") (pinfunction "SDI_4") (pintype "passive"))
      (node (ref "D23") (pin "3") (pinfunction "SDO_3") (pintype "passive"))
    )
    (net (code "49") (name "Net-(D22-SDO)") (class "Default")
      (node (ref "D22") (pin "3") (pinfunction "SDO_3") (pintype "passive"))
      (node (ref "D26") (pin "4") (pinfunction "SDI_4") (pintype "passive"))
    )
    (net (code "50") (name "Net-(D23-CKI)") (class "Default")
      (node (ref "D23") (pin "5") (pinfunction "CKI_5") (pintype "passive"))
      (node (ref "D24") (pin "2") (pinfunction "CKO_2") (pintype "passive"))
    )
    (net (code "51") (name "Net-(D23-SDI)") (class "Default")
      (node (ref "D23") (pin "4") (pinfunction "SDI_4") (pintype "passive"))
      (node (ref "D24") (pin "3") (pinfunction "SDO_3") (pintype "passive"))
    )
    (net (code "52") (name "Net-(D24-CKI)") (class "Default")
      (node (ref "D24") (pin "5") (pinfunction "CKI_5") (pintype "passive"))
      (node (ref "D25") (pin "2") (pinfunction "CKO_2") (pintype "passive"))
    )
    (net (code "53") (name "Net-(D24-SDI)") (class "Default")
      (node (ref "D24") (pin "4") (pinfunction "SDI_4") (pintype "passive"))
      (node (ref "D25") (pin "3") (pinfunction "SDO_3") (pintype "passive"))
    )
    (net (code "54") (name "Net-(D26-CKO)") (class "Default")
      (node (ref "D26") (pin "2") (pinfunction "CKO_2") (pintype "passive"))
      (node (ref "D27") (pin "5") (pinfunction "CKI_5") (pintype "passive"))
    )
    (net (code "55") (name "Net-(D26-SDO)") (class "Default")
      (node (ref "D26") (pin "3") (pinfunction "SDO_3") (pintype "passive"))
      (node (ref "D27") (pin "4") (pinfunction "SDI_4") (pintype "passive"))
    )
    (net (code "56") (name "Net-(D27-CKO)") (class "Default")
      (node (ref "D27") (pin "2") (pinfunction "CKO_2") (pintype "passive"))
      (node (ref "D28") (pin "5") (pinfunction "CKI_5") (pintype "passive"))
    )
    (net (code "57") (name "Net-(D27-SDO)") (class "Default")
      (node (ref "D27") (pin "3") (pinfunction "SDO_3") (pintype "passive"))
      (node (ref "D28") (pin "4") (pinfunction "SDI_4") (pintype "passive"))
    )
    (net (code "58") (name "Net-(D28-CKO)") (class "Default")
      (node (ref "D28") (pin "2") (pinfunction "CKO_2") (pintype "passive"))
      (node (ref "D29") (pin "5") (pinfunction "CKI_5") (pintype "passive"))
    )
    (net (code "59") (name "Net-(D28-SDO)") (class "Default")
      (node (ref "D28") (pin "3") (pinfunction "SDO_3") (pintype "passive"))
      (node (ref "D29") (pin "4") (pinfunction "SDI_4") (pintype "passive"))
    )
    (net (code "60") (name "Net-(D29-CKO)") (class "Default")
      (node (ref "D29") (pin "2") (pinfunction "CKO_2") (pintype "passive"))
      (node (ref "D30") (pin "5") (pinfunction "CKI_5") (pintype "passive"))
    )
    (net (code "61") (name "Net-(D29-SDO)") (class "Default")
      (node (ref "D29") (pin "3") (pinfunction "SDO_3") (pintype "passive"))
      (node (ref "D30") (pin "4") (pinfunction "SDI_4") (pintype "passive"))
    )
    (net (code "62") (name "Net-(D30-CKO)") (class "Default")
      (node (ref "D30") (pin "2") (pinfunction "CKO_2") (pintype "passive"))
      (node (ref "D31") (pin "5") (pinfunction "CKI_5") (pintype "passive"))
    )
    (net (code "63") (name "Net-(D30-SDO)") (class "Default")
      (node (ref "D30") (pin "3") (pinfunction "SDO_3") (pintype "passive"))
      (node (ref "D31") (pin "4") (pinfunction "SDI_4") (pintype "passive"))
    )
    (net (code "64") (name "Net-(D31-CKO)") (class "Default")
      (node (ref "D31") (pin "2") (pinfunction "CKO_2") (pintype "passive"))
      (node (ref "D32") (pin "5") (pinfunction "CKI_5") (pintype "passive"))
    )
    (net (code "65") (name "Net-(D31-SDO)") (class "Default")
      (node (ref "D31") (pin "3") (pinfunction "SDO_3") (pintype "passive"))
      (node (ref "D32") (pin "4") (pinfunction "SDI_4") (pintype "passive"))
    )
    (net (code "66") (name "Net-(D32-CKO)") (class "Default")
      (node (ref "D32") (pin "2") (pinfunction "CKO_2") (pintype "passive"))
      (node (ref "D33") (pin "5") (pinfunction "CKI_5") (pintype "passive"))
    )
    (net (code "67") (name "Net-(D32-SDO)") (class "Default")
      (node (ref "D32") (pin "3") (pinfunction "SDO_3") (pintype "passive"))
      (node (ref "D33") (pin "4") (pinfunction "SDI_4") (pintype "passive"))
    )
    (net (code "68") (name "Net-(D33-CKO)") (class "Default")
      (node (ref "D33") (pin "2") (pinfunction "CKO_2") (pintype "passive"))
      (node (ref "D34") (pin "5") (pinfunction "CKI_5") (pintype "passive"))
    )
    (net (code "69") (name "Net-(D33-SDO)") (class "Default")
      (node (ref "D33") (pin "3") (pinfunction "SDO_3") (pintype "passive"))
      (node (ref "D34") (pin "4") (pinfunction "SDI_4") (pintype "passive"))
    )
    (net (code "70") (name "Net-(D34-CKO)") (class "Default")
      (node (ref "D34") (pin "2") (pinfunction "CKO_2") (pintype "passive"))
      (node (ref "D35") (pin "5") (pinfunction "CKI_5") (pintype "passive"))
    )
    (net (code "71") (name "Net-(D34-SDO)") (class "Default")
      (node (ref "D34") (pin "3") (pinfunction "SDO_3") (pintype "passive"))
      (node (ref "D35") (pin "4") (pinfunction "SDI_4") (pintype "passive"))
    )
    (net (code "72") (name "Net-(D35-CKO)") (class "Default")
      (node (ref "D35") (pin "2") (pinfunction "CKO_2") (pintype "passive"))
      (node (ref "D36") (pin "5") (pinfunction "CKI_5") (pintype "passive"))
    )
    (net (code "73") (name "Net-(D35-SDO)") (class "Default")
      (node (ref "D35") (pin "3") (pinfunction "SDO_3") (pintype "passive"))
      (node (ref "D36") (pin "4") (pinfunction "SDI_4") (pintype "passive"))
    )
    (net (code "74") (name "Net-(D36-CKO)") (class "Default")
      (node (ref "D36") (pin "2") (pinfunction "CKO_2") (pintype "passive"))
      (node (ref "D37") (pin "5") (pinfunction "CKI_5") (pintype "passive"))
    )
    (net (code "75") (name "Net-(D36-SDO)") (class "Default")
      (node (ref "D36") (pin "3") (pinfunction "SDO_3") (pintype "passive"))
      (node (ref "D37") (pin "4") (pinfunction "SDI_4") (pintype "passive"))
    )
    (net (code "76") (name "Net-(D37-CKO)") (class "Default")
      (node (ref "D37") (pin "2") (pinfunction "CKO_2") (pintype "passive"))
      (node (ref "D38") (pin "5") (pinfunction "CKI_5") (pintype "passive"))
    )
    (net (code "77") (name "Net-(D37-SDO)") (class "Default")
      (node (ref "D37") (pin "3") (pinfunction "SDO_3") (pintype "passive"))
      (node (ref "D38") (pin "4") (pinfunction "SDI_4") (pintype "passive"))
    )
    (net (code "78") (name "Net-(D38-CKO)") (class "Default")
      (node (ref "D38") (pin "2") (pinfunction "CKO_2") (pintype "passive"))
      (node (ref "D39") (pin "5") (pinfunction "CKI_5") (pintype "passive"))
    )
    (net (code "79") (name "Net-(D38-SDO)") (class "Default")
      (node (ref "D38") (pin "3") (pinfunction "SDO_3") (pintype "passive"))
      (node (ref "D39") (pin "4") (pinfunction "SDI_4") (pintype "passive"))
    )
    (net (code "80") (name "Net-(D39-CKO)") (class "Default")
      (node (ref "D39") (pin "2") (pinfunction "CKO_2") (pintype "passive"))
      (node (ref "D45") (pin "5") (pinfunction "CKI_5") (pintype "passive"))
    )
    (net (code "81") (name "Net-(D39-SDO)") (class "Default")
      (node (ref "D39") (pin "3") (pinfunction "SDO_3") (pintype "passive"))
      (node (ref "D45") (pin "4") (pinfunction "SDI_4") (pintype "passive"))
    )
    (net (code "82") (name "Net-(D40-CKI)") (class "Default")
      (node (ref "D40") (pin "5") (pinfunction "CKI_5") (pintype "passive"))
      (node (ref "D41") (pin "2") (pinfunction "CKO_2") (pintype "passive"))
    )
    (net (code "83") (name "Net-(D40-CKO)") (class "Default")
      (node (ref "D40") (pin "2") (pinfunction "CKO_2") (pintype "passive"))
      (node (ref "D46") (pin "5") (pinfunction "CKI_5") (pintype "passive"))
    )
    (net (code "84") (name "Net-(D40-SDI)") (class "Default")
      (node (ref "D40") (pin "4") (pinfunction "SDI_4") (pintype "passive"))
      (node (ref "D41") (pin "3") (pinfunction "SDO_3") (pintype "passive"))
    )
    (net (code "85") (name "Net-(D40-SDO)") (class "Default")
      (node (ref "D40") (pin "3") (pinfunction "SDO_3") (pintype "passive"))
      (node (ref "D46") (pin "4") (pinfunction "SDI_4") (pintype "passive"))
    )
    (net (code "86") (name "Net-(D41-CKI)") (class "Default")
      (node (ref "D41") (pin "5") (pinfunction "CKI_5") (pintype "passive"))
      (node (ref "D42") (pin "2") (pinfunction "CKO_2") (pintype "passive"))
    )
    (net (code "87") (name "Net-(D41-SDI)") (class "Default")
      (node (ref "D41") (pin "4") (pinfunction "SDI_4") (pintype "passive"))
      (node (ref "D42") (pin "3") (pinfunction "SDO_3") (pintype "passive"))
    )
    (net (code "88") (name "Net-(D42-CKI)") (class "Default")
      (node (ref "D42") (pin "5") (pinfunction "CKI_5") (pintype "passive"))
      (node (ref "D43") (pin "2") (pinfunction "CKO_2") (pintype "passive"))
    )
    (net (code "89") (name "Net-(D42-SDI)") (class "Default")
      (node (ref "D42") (pin "4") (pinfunction "SDI_4") (pintype "passive"))
      (node (ref "D43") (pin "3") (pinfunction "SDO_3") (pintype "passive"))
    )
    (net (code "90") (name "Net-(D43-CKI)") (class "Default")
      (node (ref "D43") (pin "5") (pinfunction "CKI_5") (pintype "passive"))
      (node (ref "D44") (pin "2") (pinfunction "CKO_2") (pintype "passive"))
    )
    (net (code "91") (name "Net-(D43-SDI)") (class "Default")
      (node (ref "D43") (pin "4") (pinfunction "SDI_4") (pintype "passive"))
      (node (ref "D44") (pin "3") (pinfunction "SDO_3") (pintype "passive"))
    )
    (net (code "92") (name "Net-(D44-CKI)") (class "Default")
      (node (ref "D44") (pin "5") (pinfunction "CKI_5") (pintype "passive"))
      (node (ref "D45") (pin "2") (pinfunction "CKO_2") (pintype "passive"))
    )
    (net (code "93") (name "Net-(D44-SDI)") (class "Default")
      (node (ref "D44") (pin "4") (pinfunction "SDI_4") (pintype "passive"))
      (node (ref "D45") (pin "3") (pinfunction "SDO_3") (pintype "passive"))
    )
    (net (code "94") (name "Net-(D46-CKO)") (class "Default")
      (node (ref "D46") (pin "2") (pinfunction "CKO_2") (pintype "passive"))
      (node (ref "D47") (pin "5") (pinfunction "CKI_5") (pintype "passive"))
    )
    (net (code "95") (name "Net-(D46-SDO)") (class "Default")
      (node (ref "D46") (pin "3") (pinfunction "SDO_3") (pintype "passive"))
      (node (ref "D47") (pin "4") (pinfunction "SDI_4") (pintype "passive"))
    )
    (net (code "96") (name "Net-(D47-CKO)") (class "Default")
      (node (ref "D47") (pin "2") (pinfunction "CKO_2") (pintype "passive"))
      (node (ref "D51") (pin "5") (pinfunction "CKI_5") (pintype "passive"))
    )
    (net (code "97") (name "Net-(D47-SDO)") (class "Default")
      (node (ref "D47") (pin "3") (pinfunction "SDO_3") (pintype "passive"))
      (node (ref "D51") (pin "4") (pinfunction "SDI_4") (pintype "passive"))
    )
    (net (code "98") (name "Net-(D48-CKI)") (class "Default")
      (node (ref "D48") (pin "5") (pinfunction "CKI_5") (pintype "passive"))
      (node (ref "D49") (pin "2") (pinfunction "CKO_2") (pintype "passive"))
    )
    (net (code "99") (name "Net-(D48-CKO)") (class "Default")
      (node (ref "D48") (pin "2") (pinfunction "CKO_2") (pintype "passive"))
      (node (ref "D52") (pin "5") (pinfunction "CKI_5") (pintype "passive"))
    )
    (net (code "100") (name "Net-(D48-SDI)") (class "Default")
      (node (ref "D48") (pin "4") (pinfunction "SDI_4") (pintype "passive"))
      (node (ref "D49") (pin "3") (pinfunction "SDO_3") (pintype "passive"))
    )
    (net (code "101") (name "Net-(D48-SDO)") (class "Default")
      (node (ref "D48") (pin "3") (pinfunction "SDO_3") (pintype "passive"))
      (node (ref "D52") (pin "4") (pinfunction "SDI_4") (pintype "passive"))
    )
    (net (code "102") (name "Net-(D49-CKI)") (class "Default")
      (node (ref "D49") (pin "5") (pinfunction "CKI_5") (pintype "passive"))
      (node (ref "D50") (pin "2") (pinfunction "CKO_2") (pintype "passive"))
    )
    (net (code "103") (name "Net-(D49-SDI)") (class "Default")
      (node (ref "D49") (pin "4") (pinfunction "SDI_4") (pintype "passive"))
      (node (ref "D50") (pin "3") (pinfunction "SDO_3") (pintype "passive"))
    )
    (net (code "104") (name "Net-(D50-CKI)") (class "Default")
      (node (ref "D50") (pin "5") (pinfunction "CKI_5") (pintype "passive"))
      (node (ref "D51") (pin "2") (pinfunction "CKO_2") (pintype "passive"))
    )
    (net (code "105") (name "Net-(D50-SDI)") (class "Default")
      (node (ref "D50") (pin "4") (pinfunction "SDI_4") (pintype "passive"))
      (node (ref "D51") (pin "3") (pinfunction "SDO_3") (pintype "passive"))
    )
    (net (code "106") (name "Net-(D52-CKO)") (class "Default")
      (node (ref "D52") (pin "2") (pinfunction "CKO_2") (pintype "passive"))
      (node (ref "D53") (pin "5") (pinfunction "CKI_5") (pintype "passive"))
    )
    (net (code "107") (name "Net-(D52-SDO)") (class "Default")
      (node (ref "D52") (pin "3") (pinfunction "SDO_3") (pintype "passive"))
      (node (ref "D53") (pin "4") (pinfunction "SDI_4") (pintype "passive"))
    )
    (net (code "108") (name "Net-(D53-CKO)") (class "Default")
      (node (ref "D53") (pin "2") (pinfunction "CKO_2") (pintype "passive"))
      (node (ref "D54") (pin "5") (pinfunction "CKI_5") (pintype "passive"))
    )
    (net (code "109") (name "Net-(D53-SDO)") (class "Default")
      (node (ref "D53") (pin "3") (pinfunction "SDO_3") (pintype "passive"))
      (node (ref "D54") (pin "4") (pinfunction "SDI_4") (pintype "passive"))
    )
    (net (code "110") (name "Net-(D54-CKO)") (class "Default")
      (node (ref "D54") (pin "2") (pinfunction "CKO_2") (pintype "passive"))
      (node (ref "D55") (pin "5") (pinfunction "CKI_5") (pintype "passive"))
    )
    (net (code "111") (name "Net-(D54-SDO)") (class "Default")
      (node (ref "D54") (pin "3") (pinfunction "SDO_3") (pintype "passive"))
      (node (ref "D55") (pin "4") (pinfunction "SDI_4") (pintype "passive"))
    )
    (net (code "112") (name "Net-(D55-CKO)") (class "Default")
      (node (ref "D55") (pin "2") (pinfunction "CKO_2") (pintype "passive"))
      (node (ref "D56") (pin "5") (pinfunction "CKI_5") (pintype "passive"))
    )
    (net (code "113") (name "Net-(D55-SDO)") (class "Default")
      (node (ref "D55") (pin "3") (pinfunction "SDO_3") (pintype "passive"))
      (node (ref "D56") (pin "4") (pinfunction "SDI_4") (pintype "passive"))
    )
    (net (code "114") (name "Net-(D56-CKO)") (class "Default")
      (node (ref "D56") (pin "2") (pinfunction "CKO_2") (pintype "passive"))
      (node (ref "D57") (pin "5") (pinfunction "CKI_5") (pintype "passive"))
    )
    (net (code "115") (name "Net-(D56-SDO)") (class "Default")
      (node (ref "D56") (pin "3") (pinfunction "SDO_3") (pintype "passive"))
      (node (ref "D57") (pin "4") (pinfunction "SDI_4") (pintype "passive"))
    )
    (net (code "116") (name "Net-(D57-CKO)") (class "Default")
      (node (ref "D57") (pin "2") (pinfunction "CKO_2") (pintype "passive"))
      (node (ref "D58") (pin "5") (pinfunction "CKI_5") (pintype "passive"))
    )
    (net (code "117") (name "Net-(D57-SDO)") (class "Default")
      (node (ref "D57") (pin "3") (pinfunction "SDO_3") (pintype "passive"))
      (node (ref "D58") (pin "4") (pinfunction "SDI_4") (pintype "passive"))
    )
    (net (code "118") (name "Net-(D58-CKO)") (class "Default")
      (node (ref "D58") (pin "2") (pinfunction "CKO_2") (pintype "passive"))
      (node (ref "D59") (pin "5") (pinfunction "CKI_5") (pintype "passive"))
    )
    (net (code "119") (name "Net-(D58-SDO)") (class "Default")
      (node (ref "D58") (pin "3") (pinfunction "SDO_3") (pintype "passive"))
      (node (ref "D59") (pin "4") (pinfunction "SDI_4") (pintype "passive"))
    )
    (net (code "120") (name "Net-(D59-CKO)") (class "Default")
      (node (ref "D59") (pin "2") (pinfunction "CKO_2") (pintype "passive"))
      (node (ref "D60") (pin "5") (pinfunction "CKI_5") (pintype "passive"))
    )
    (net (code "121") (name "Net-(D59-SDO)") (class "Default")
      (node (ref "D59") (pin "3") (pinfunction "SDO_3") (pintype "passive"))
      (node (ref "D60") (pin "4") (pinfunction "SDI_4") (pintype "passive"))
    )
    (net (code "122") (name "Net-(D60-CKO)") (class "Default")
      (node (ref "D60") (pin "2") (pinfunction "CKO_2") (pintype "passive"))
      (node (ref "D61") (pin "5") (pinfunction "CKI_5") (pintype "passive"))
    )
    (net (code "123") (name "Net-(D60-SDO)") (class "Default")
      (node (ref "D60") (pin "3") (pinfunction "SDO_3") (pintype "passive"))
      (node (ref "D61") (pin "4") (pinfunction "SDI_4") (pintype "passive"))
    )
    (net (code "124") (name "Net-(D61-CKO)") (class "Default")
      (node (ref "D61") (pin "2") (pinfunction "CKO_2") (pintype "passive"))
      (node (ref "D62") (pin "5") (pinfunction "CKI_5") (pintype "passive"))
    )
    (net (code "125") (name "Net-(D61-SDO)") (class "Default")
      (node (ref "D61") (pin "3") (pinfunction "SDO_3") (pintype "passive"))
      (node (ref "D62") (pin "4") (pinfunction "SDI_4") (pintype "passive"))
    )
    (net (code "126") (name "Net-(D62-CKO)") (class "Default")
      (node (ref "D62") (pin "2") (pinfunction "CKO_2") (pintype "passive"))
      (node (ref "D63") (pin "5") (pinfunction "CKI_5") (pintype "passive"))
    )
    (net (code "127") (name "Net-(D62-SDO)") (class "Default")
      (node (ref "D62") (pin "3") (pinfunction "SDO_3") (pintype "passive"))
      (node (ref "D63") (pin "4") (pinfunction "SDI_4") (pintype "passive"))
    )
    (net (code "128") (name "Net-(D63-CKO)") (class "Default")
      (node (ref "D63") (pin "2") (pinfunction "CKO_2") (pintype "passive"))
      (node (ref "D64") (pin "5") (pinfunction "CKI_5") (pintype "passive"))
    )
    (net (code "129") (name "Net-(D63-SDO)") (class "Default")
      (node (ref "D63") (pin "3") (pinfunction "SDO_3") (pintype "passive"))
      (node (ref "D64") (pin "4") (pinfunction "SDI_4") (pintype "passive"))
    )
    (net (code "130") (name "Net-(D64-CKO)") (class "Default")
      (node (ref "D64") (pin "2") (pinfunction "CKO_2") (pintype "passive"))
      (node (ref "D65") (pin "5") (pinfunction "CKI_5") (pintype "passive"))
    )
    (net (code "131") (name "Net-(D64-SDO)") (class "Default")
      (node (ref "D64") (pin "3") (pinfunction "SDO_3") (pintype "passive"))
      (node (ref "D65") (pin "4") (pinfunction "SDI_4") (pintype "passive"))
    )
    (net (code "132") (name "Net-(D65-CKO)") (class "Default")
      (node (ref "D65") (pin "2") (pinfunction "CKO_2") (pintype "passive"))
      (node (ref "D66") (pin "5") (pinfunction "CKI_5") (pintype "passive"))
    )
    (net (code "133") (name "Net-(D65-SDO)") (class "Default")
      (node (ref "D65") (pin "3") (pinfunction "SDO_3") (pintype "passive"))
      (node (ref "D66") (pin "4") (pinfunction "SDI_4") (pintype "passive"))
    )
    (net (code "134") (name "Net-(D66-CKO)") (class "Default")
      (node (ref "D66") (pin "2") (pinfunction "CKO_2") (pintype "passive"))
      (node (ref "D67") (pin "5") (pinfunction "CKI_5") (pintype "passive"))
    )
    (net (code "135") (name "Net-(D66-SDO)") (class "Default")
      (node (ref "D66") (pin "3") (pinfunction "SDO_3") (pintype "passive"))
      (node (ref "D67") (pin "4") (pinfunction "SDI_4") (pintype "passive"))
    )
    (net (code "136") (name "Net-(D67-CKO)") (class "Default")
      (node (ref "D67") (pin "2") (pinfunction "CKO_2") (pintype "passive"))
      (node (ref "D68") (pin "5") (pinfunction "CKI_5") (pintype "passive"))
    )
    (net (code "137") (name "Net-(D67-SDO)") (class "Default")
      (node (ref "D67") (pin "3") (pinfunction "SDO_3") (pintype "passive"))
      (node (ref "D68") (pin "4") (pinfunction "SDI_4") (pintype "passive"))
    )
    (net (code "138") (name "Net-(D68-CKO)") (class "Default")
      (node (ref "D68") (pin "2") (pinfunction "CKO_2") (pintype "passive"))
      (node (ref "D69") (pin "5") (pinfunction "CKI_5") (pintype "passive"))
    )
    (net (code "139") (name "Net-(D68-SDO)") (class "Default")
      (node (ref "D68") (pin "3") (pinfunction "SDO_3") (pintype "passive"))
      (node (ref "D69") (pin "4") (pinfunction "SDI_4") (pintype "passive"))
    )
    (net (code "140") (name "Net-(D69-CKO)") (class "Default")
      (node (ref "D69") (pin "2") (pinfunction "CKO_2") (pintype "passive"))
      (node (ref "D70") (pin "5") (pinfunction "CKI_5") (pintype "passive"))
    )
    (net (code "141") (name "Net-(D69-SDO)") (class "Default")
      (node (ref "D69") (pin "3") (pinfunction "SDO_3") (pintype "passive"))
      (node (ref "D70") (pin "4") (pinfunction "SDI_4") (pintype "passive"))
    )
    (net (code "142") (name "Net-(D70-CKO)") (class "Default")
      (node (ref "D70") (pin "2") (pinfunction "CKO_2") (pintype "passive"))
      (node (ref "D71") (pin "5") (pinfunction "CKI_5") (pintype "passive"))
    )
    (net (code "143") (name "Net-(D70-SDO)") (class "Default")
      (node (ref "D70") (pin "3") (pinfunction "SDO_3") (pintype "passive"))
      (node (ref "D71") (pin "4") (pinfunction "SDI_4") (pintype "passive"))
    )
    (net (code "144") (name "Net-(D71-CKO)") (class "Default")
      (node (ref "D71") (pin "2") (pinfunction "CKO_2") (pintype "passive"))
      (node (ref "D72") (pin "5") (pinfunction "CKI_5") (pintype "passive"))
    )
    (net (code "145") (name "Net-(D71-SDO)") (class "Default")
      (node (ref "D71") (pin "3") (pinfunction "SDO_3") (pintype "passive"))
      (node (ref "D72") (pin "4") (pinfunction "SDI_4") (pintype "passive"))
    )
    (net (code "146") (name "Net-(D72-CKO)") (class "Default")
      (node (ref "D72") (pin "2") (pinfunction "CKO_2") (pintype "passive"))
      (node (ref "D73") (pin "5") (pinfunction "CKI_5") (pintype "passive"))
    )
    (net (code "147") (name "Net-(D72-SDO)") (class "Default")
      (node (ref "D72") (pin "3") (pinfunction "SDO_3") (pintype "passive"))
      (node (ref "D73") (pin "4") (pinfunction "SDI_4") (pintype "passive"))
    )
    (net (code "148") (name "Net-(D73-CKO)") (class "Default")
      (node (ref "D73") (pin "2") (pinfunction "CKO_2") (pintype "passive"))
      (node (ref "D74") (pin "5") (pinfunction "CKI_5") (pintype "passive"))
    )
    (net (code "149") (name "Net-(D73-SDO)") (class "Default")
      (node (ref "D73") (pin "3") (pinfunction "SDO_3") (pintype "passive"))
      (node (ref "D74") (pin "4") (pinfunction "SDI_4") (pintype "passive"))
    )
    (net (code "150") (name "Net-(D74-CKO)") (class "Default")
      (node (ref "D74") (pin "2") (pinfunction "CKO_2") (pintype "passive"))
      (node (ref "D75") (pin "5") (pinfunction "CKI_5") (pintype "passive"))
    )
    (net (code "151") (name "Net-(D74-SDO)") (class "Default")
      (node (ref "D74") (pin "3") (pinfunction "SDO_3") (pintype "passive"))
      (node (ref "D75") (pin "4") (pinfunction "SDI_4") (pintype "passive"))
    )
    (net (code "152") (name "Net-(D75-CKO)") (class "Default")
      (node (ref "D75") (pin "2") (pinfunction "CKO_2") (pintype "passive"))
      (node (ref "D76") (pin "5") (pinfunction "CKI_5") (pintype "passive"))
    )
    (net (code "153") (name "Net-(D75-SDO)") (class "Default")
      (node (ref "D75") (pin "3") (pinfunction "SDO_3") (pintype "passive"))
      (node (ref "D76") (pin "4") (pinfunction "SDI_4") (pintype "passive"))
    )
    (net (code "154") (name "Net-(D76-CKO)") (class "Default")
      (node (ref "D76") (pin "2") (pinfunction "CKO_2") (pintype "passive"))
      (node (ref "D81") (pin "5") (pinfunction "CKI_5") (pintype "passive"))
    )
    (net (code "155") (name "Net-(D76-SDO)") (class "Default")
      (node (ref "D76") (pin "3") (pinfunction "SDO_3") (pintype "passive"))
      (node (ref "D81") (pin "4") (pinfunction "SDI_4") (pintype "passive"))
    )
    (net (code "156") (name "Net-(D77-CKI)") (class "Default")
      (node (ref "D77") (pin "5") (pinfunction "CKI_5") (pintype "passive"))
      (node (ref "D78") (pin "2") (pinfunction "CKO_2") (pintype "passive"))
    )
    (net (code "157") (name "Net-(D77-CKO)") (class "Default")
      (node (ref "D77") (pin "2") (pinfunction "CKO_2") (pintype "passive"))
      (node (ref "D82") (pin "5") (pinfunction "CKI_5") (pintype "passive"))
    )
    (net (code "158") (name "Net-(D77-SDI)") (class "Default")
      (node (ref "D77") (pin "4") (pinfunction "SDI_4") (pintype "passive"))
      (node (ref "D78") (pin "3") (pinfunction "SDO_3") (pintype "passive"))
    )
    (net (code "159") (name "Net-(D77-SDO)") (class "Default")
      (node (ref "D77") (pin "3") (pinfunction "SDO_3") (pintype "passive"))
      (node (ref "D82") (pin "4") (pinfunction "SDI_4") (pintype "passive"))
    )
    (net (code "160") (name "Net-(D78-CKI)") (class "Default")
      (node (ref "D78") (pin "5") (pinfunction "CKI_5") (pintype "passive"))
      (node (ref "D79") (pin "2") (pinfunction "CKO_2") (pintype "passive"))
    )
    (net (code "161") (name "Net-(D78-SDI)") (class "Default")
      (node (ref "D78") (pin "4") (pinfunction "SDI_4") (pintype "passive"))
      (node (ref "D79") (pin "3") (pinfunction "SDO_3") (pintype "passive"))
    )
    (net (code "162") (name "Net-(D79-CKI)") (class "Default")
      (node (ref "D79") (pin "5") (pinfunction "CKI_5") (pintype "passive"))
      (node (ref "D80") (pin "2") (pinfunction "CKO_2") (pintype "passive"))
    )
    (net (code "163") (name "Net-(D79-SDI)") (class "Default")
      (node (ref "D79") (pin "4") (pinfunction "SDI_4") (pintype "passive"))
      (node (ref "D80") (pin "3") (pinfunction "SDO_3") (pintype "passive"))
    )
    (net (code "164") (name "Net-(D80-CKI)") (class "Default")
      (node (ref "D80") (pin "5") (pinfunction "CKI_5") (pintype "passive"))
      (node (ref "D81") (pin "2") (pinfunction "CKO_2") (pintype "passive"))
    )
    (net (code "165") (name "Net-(D80-SDI)") (class "Default")
      (node (ref "D80") (pin "4") (pinfunction "SDI_4") (pintype "passive"))
      (node (ref "D81") (pin "3") (pinfunction "SDO_3") (pintype "passive"))
    )
    (net (code "166") (name "VDD") (class "Default")
      (node (ref "C11") (pin "2") (pinfunction "2_2") (pintype "passive"))
      (node (ref "C12") (pin "2") (pinfunction "2_2") (pintype "passive"))
      (node (ref "C13") (pin "2") (pinfunction "2_2") (pintype "passive"))
      (node (ref "C14") (pin "2") (pinfunction "2_2") (pintype "passive"))
      (node (ref "C15") (pin "2") (pinfunction "2_2") (pintype "passive"))
      (node (ref "C16") (pin "2") (pinfunction "2_2") (pintype "passive"))
      (node (ref "C17") (pin "2") (pinfunction "2_2") (pintype "passive"))
      (node (ref "C18") (pin "2") (pinfunction "2_2") (pintype "passive"))
      (node (ref "C19") (pin "2") (pinfunction "2_2") (pintype "passive"))
      (node (ref "C20") (pin "2") (pinfunction "2_2") (pintype "passive"))
      (node (ref "C21") (pin "2") (pinfunction "2_2") (pintype "passive"))
      (node (ref "C22") (pin "2") (pinfunction "2_2") (pintype "passive"))
      (node (ref "C23") (pin "2") (pinfunction "2_2") (pintype "passive"))
      (node (ref "C24") (pin "2") (pinfunction "2_2") (pintype "passive"))
      (node (ref "C25") (pin "2") (pinfunction "2_2") (pintype "passive"))
      (node (ref "C26") (pin "2") (pinfunction "2_2") (pintype "passive"))
      (node (ref "C27") (pin "2") (pinfunction "2_2") (pintype "passive"))
      (node (ref "C28") (pin "2") (pinfunction "2_2") (pintype "passive"))
      (node (ref "C29") (pin "2") (pinfunction "2_2") (pintype "passive"))
      (node (ref "D1") (pin "1") (pinfunction "VDD_1") (pintype "passive"))
      (node (ref "D10") (pin "1") (pinfunction "VDD_1") (pintype "passive"))
      (node (ref "D11") (pin "1") (pinfunction "VDD_1") (pintype "passive"))
      (node (ref "D12") (pin "1") (pinfunction "VDD_1") (pintype "passive"))
      (node (ref "D13") (pin "1") (pinfunction "VDD_1") (pintype "passive"))
      (node (ref "D14") (pin "1") (pinfunction "VDD_1") (pintype "passive"))
      (node (ref "D15") (pin "1") (pinfunction "VDD_1") (pintype "passive"))
      (node (ref "D16") (pin "1") (pinfunction "VDD_1") (pintype "passive"))
      (node (ref "D17") (pin "1") (pinfunction "VDD_1") (pintype "passive"))
      (node (ref "D18") (pin "1") (pinfunction "VDD_1") (pintype "passive"))
      (node (ref "D19") (pin "1") (pinfunction "VDD_1") (pintype "passive"))
      (node (ref "D2") (pin "1") (pinfunction "VDD_1") (pintype "passive"))
      (node (ref "D20") (pin "1") (pinfunction "VDD_1") (pintype "passive"))
      (node (ref "D21") (pin "1") (pinfunction "VDD_1") (pintype "passive"))
      (node (ref "D22") (pin "1") (pinfunction "VDD_1") (pintype "passive"))
      (node (ref "D23") (pin "1") (pinfunction "VDD_1") (pintype "passive"))
      (node (ref "D24") (pin "1") (pinfunction "VDD_1") (pintype "passive"))
      (node (ref "D25") (pin "1") (pinfunction "VDD_1") (pintype "passive"))
      (node (ref "D26") (pin "1") (pinfunction "VDD_1") (pintype "passive"))
      (node (ref "D27") (pin "1") (pinfunction "VDD_1") (pintype "passive"))
      (node (ref "D28") (pin "1") (pinfunction "VDD_1") (pintype "passive"))
      (node (ref "D29") (pin "1") (pinfunction "VDD_1") (pintype "passive"))
      (node (ref "D3") (pin "1") (pinfunction "VDD_1") (pintype "passive"))
      (node (ref "D30") (pin "1") (pinfunction "VDD_1") (pintype "passive"))
      (node (ref "D31") (pin "1") (pinfunction "VDD_1") (pintype "passive"))
      (node (ref "D32") (pin "1") (pinfunction "VDD_1") (pintype "passive"))
      (node (ref "D33") (pin "1") (pinfunction "VDD_1") (pintype "passive"))
      (node (ref "D34") (pin "1") (pinfunction "VDD_1") (pintype "passive"))
      (node (ref "D35") (pin "1") (pinfunction "VDD_1") (pintype "passive"))
      (node (ref "D36") (pin "1") (pinfunction "VDD_1") (pintype "passive"))
      (node (ref "D37") (pin "1") (pinfunction "VDD_1") (pintype "passive"))
      (node (ref "D38") (pin "1") (pinfunction "VDD_1") (pintype "passive"))
      (node (ref "D39") (pin "1") (pinfunction "VDD_1") (pintype "passive"))
      (node (ref "D4") (pin "1") (pinfunction "VDD_1") (pintype "passive"))
      (node (ref "D40") (pin "1") (pinfunction "VDD_1") (pintype "passive"))
      (node (ref "D41") (pin "1") (pinfunction "VDD_1") (pintype "passive"))
      (node (ref "D42") (pin "1") (pinfunction "VDD_1") (pintype "passive"))
      (node (ref "D43") (pin "1") (pinfunction "VDD_1") (pintype "passive"))
      (node (ref "D44") (pin "1") (pinfunction "VDD_1") (pintype "passive"))
      (node (ref "D45") (pin "1") (pinfunction "VDD_1") (pintype "passive"))
      (node (ref "D46") (pin "1") (pinfunction "VDD_1") (pintype "passive"))
      (node (ref "D47") (pin "1") (pinfunction "VDD_1") (pintype "passive"))
      (node (ref "D48") (pin "1") (pinfunction "VDD_1") (pintype "passive"))
      (node (ref "D49") (pin "1") (pinfunction "VDD_1") (pintype "passive"))
      (node (ref "D5") (pin "1") (pinfunction "VDD_1") (pintype "passive"))
      (node (ref "D50") (pin "1") (pinfunction "VDD_1") (pintype "passive"))
      (node (ref "D51") (pin "1") (pinfunction "VDD_1") (pintype "passive"))
      (node (ref "D52") (pin "1") (pinfunction "VDD_1") (pintype "passive"))
      (node (ref "D53") (pin "1") (pinfunction "VDD_1") (pintype "passive"))
      (node (ref "D54") (pin "1") (pinfunction "VDD_1") (pintype "passive"))
      (node (ref "D55") (pin "1") (pinfunction "VDD_1") (pintype "passive"))
      (node (ref "D56") (pin "1") (pinfunction "VDD_1") (pintype "passive"))
      (node (ref "D57") (pin "1") (pinfunction "VDD_1") (pintype "passive"))
      (node (ref "D58") (pin "1") (pinfunction "VDD_1") (pintype "passive"))
      (node (ref "D59") (pin "1") (pinfunction "VDD_1") (pintype "passive"))
      (node (ref "D6") (pin "1") (pinfunction "VDD_1") (pintype "passive"))
      (node (ref "D60") (pin "1") (pinfunction "VDD_1") (pintype "passive"))
      (node (ref "D61") (pin "1") (pinfunction "VDD_1") (pintype "passive"))
      (node (ref "D62") (pin "1") (pinfunction "VDD_1") (pintype "passive"))
      (node (ref "D63") (pin "1") (pinfunction "VDD_1") (pintype "passive"))
      (node (ref "D64") (pin "1") (pinfunction "VDD_1") (pintype "passive"))
      (node (ref "D65") (pin "1") (pinfunction "VDD_1") (pintype "passive"))
      (node (ref "D66") (pin "1") (pinfunction "VDD_1") (pintype "passive"))
      (node (ref "D67") (pin "1") (pinfunction "VDD_1") (pintype "passive"))
      (node (ref "D68") (pin "1") (pinfunction "VDD_1") (pintype "passive"))
      (node (ref "D69") (pin "1") (pinfunction "VDD_1") (pintype "passive"))
      (node (ref "D7") (pin "1") (pinfunction "VDD_1") (pintype "passive"))
      (node (ref "D70") (pin "1") (pinfunction "VDD_1") (pintype "passive"))
      (node (ref "D71") (pin "1") (pinfunction "VDD_1") (pintype "passive"))
      (node (ref "D72") (pin "1") (pinfunction "VDD_1") (pintype "passive"))
      (node (ref "D73") (pin "1") (pinfunction "VDD_1") (pintype "passive"))
      (node (ref "D74") (pin "1") (pinfunction "VDD_1") (pintype "passive"))
      (node (ref "D75") (pin "1") (pinfunction "VDD_1") (pintype "passive"))
      (node (ref "D76") (pin "1") (pinfunction "VDD_1") (pintype "passive"))
      (node (ref "D77") (pin "1") (pinfunction "VDD_1") (pintype "passive"))
      (node (ref "D78") (pin "1") (pinfunction "VDD_1") (pintype "passive"))
      (node (ref "D79") (pin "1") (pinfunction "VDD_1") (pintype "passive"))
      (node (ref "D8") (pin "1") (pinfunction "VDD_1") (pintype "passive"))
      (node (ref "D80") (pin "1") (pinfunction "VDD_1") (pintype "passive"))
      (node (ref "D81") (pin "1") (pinfunction "VDD_1") (pintype "passive"))
      (node (ref "D82") (pin "1") (pinfunction "VDD_1") (pintype "passive"))
      (node (ref "D9") (pin "1") (pinfunction "VDD_1") (pintype "passive"))
    )
    (net (code "167") (name "unconnected-(D82-CKO-Pad2)") (class "Default")
      (node (ref "D82") (pin "2") (pinfunction "CKO_2") (pintype "passive"))
    )
    (net (code "168") (name "unconnected-(D82-SDO-Pad3)") (class "Default")
      (node (ref "D82") (pin "3") (pinfunction "SDO_3") (pintype "passive"))
    )
  )
)
